# ActiTouch_Transmitter_Sheet1.net
KiCad netlist of a schematic drawn in Altium Designer
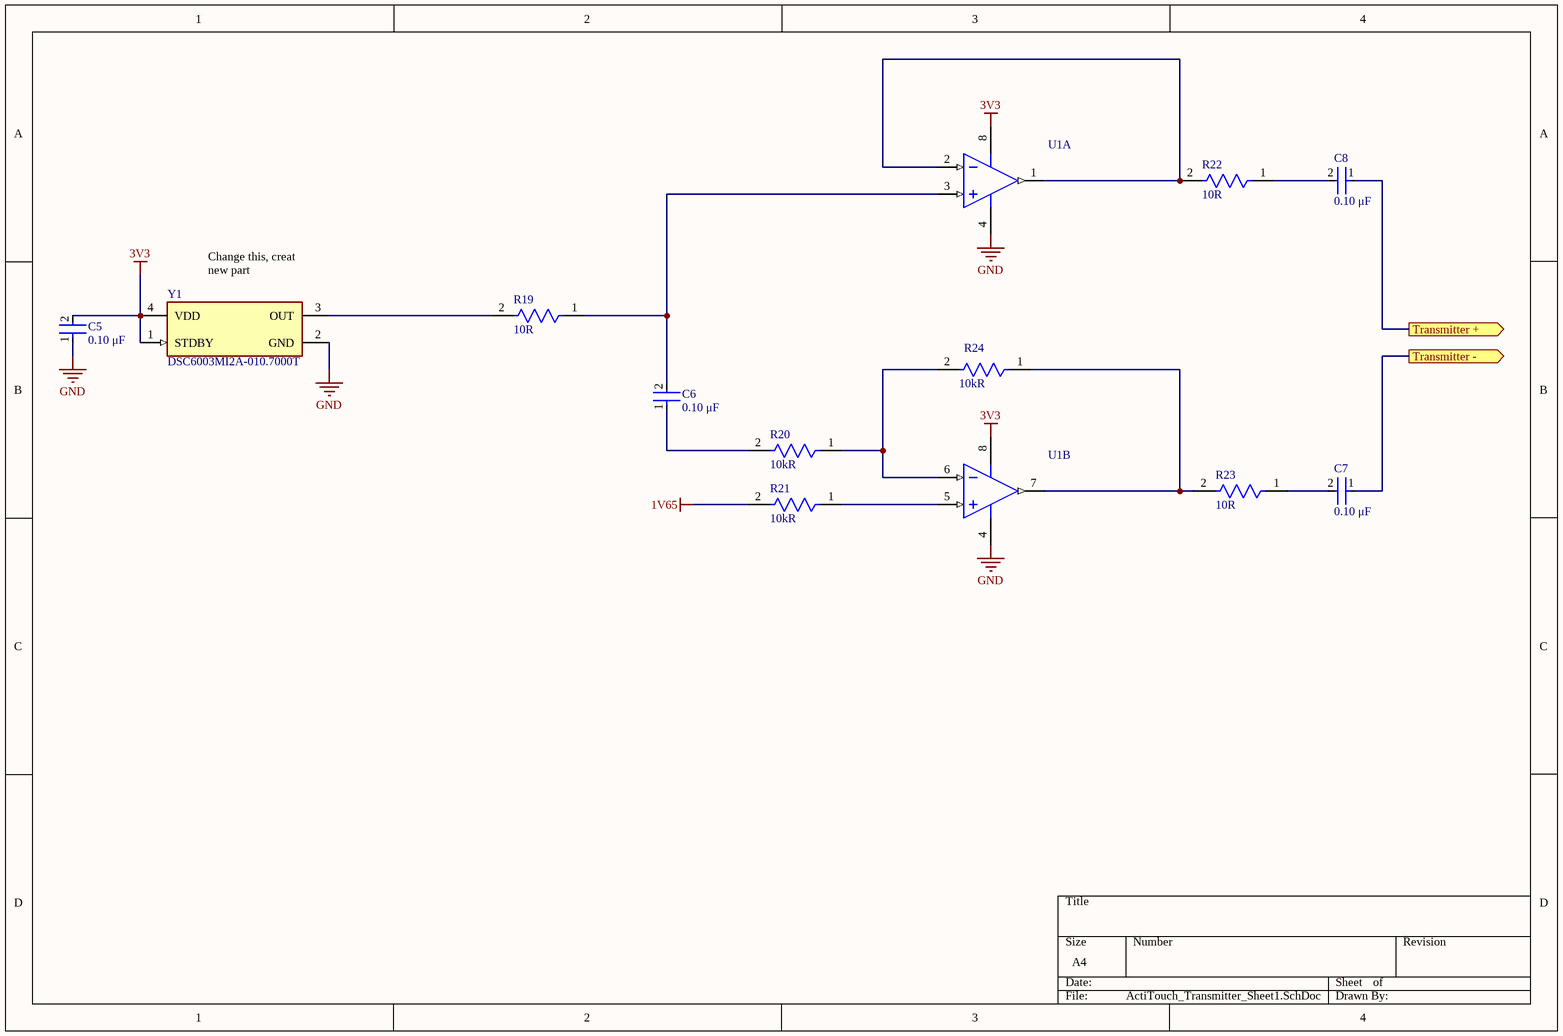
[diagram p0: ActiTouch_Transmitter_Sheet1.SchDoc]

(export (version "E")
  (design (tool "Eeschema 10.0.6"))
  (components
    (comp (ref "C5")
      (value "0.10 μF")
      (footprint "FP-C0603C-CF-MFG")
      (description "CAP CER 0.1UF 50V X7R 0603")
      (fields (field (name "TOLERANCE") "0.1") (field (name "MANUFACTURER") "KEMET"))
      (libsource (lib "Altium Content Vault") (part "b4654b650e69147ec39a6b967a45e02"))
    )
    (comp (ref "C6")
      (value "0.10 μF")
      (footprint "FP-C0603C-CF-MFG")
      (description "CAP CER 0.1UF 50V X7R 0603")
      (fields (field (name "TOLERANCE") "0.1") (field (name "MANUFACTURER") "KEMET"))
      (libsource (lib "Altium Content Vault") (part "b4654b650e69147ec39a6b967a45e02"))
    )
    (comp (ref "C7")
      (value "0.10 μF")
      (footprint "FP-C0603C-CF-MFG")
      (description "CAP CER 0.1UF 50V X7R 0603")
      (fields (field (name "TOLERANCE") "0.1") (field (name "MANUFACTURER") "KEMET"))
      (libsource (lib "Altium Content Vault") (part "b4654b650e69147ec39a6b967a45e02"))
    )
    (comp (ref "C8")
      (value "0.10 μF")
      (footprint "FP-C0603C-CF-MFG")
      (description "CAP CER 0.1UF 50V X7R 0603")
      (fields (field (name "TOLERANCE") "0.1") (field (name "MANUFACTURER") "KEMET"))
      (libsource (lib "Altium Content Vault") (part "b4654b650e69147ec39a6b967a45e02"))
    )
    (comp (ref "R19")
      (value "ESR03EZPJ101")
      (footprint "FP-ESR03-MFG")
      (description "100Ω ±5% 0.25W 0603 Anti-Surge Chip Resistor AEC-Q200")
      (fields (field (name "TOLERANCE") "5%") (field (name "RESISTANCE") "10R"))
      (libsource (lib "Altium Content Vault") (part "1029c3af85768c4190bb7ad29bc67b5"))
    )
    (comp (ref "R20")
      (value "ESR03EZPJ101")
      (footprint "FP-ESR03-MFG")
      (description "100Ω ±5% 0.25W 0603 Anti-Surge Chip Resistor AEC-Q200")
      (fields (field (name "TOLERANCE") "5%") (field (name "RESISTANCE") "10kR"))
      (libsource (lib "Altium Content Vault") (part "1029c3af85768c4190bb7ad29bc67b5"))
    )
    (comp (ref "R21")
      (value "ESR03EZPJ101")
      (footprint "FP-ESR03-MFG")
      (description "100Ω ±5% 0.25W 0603 Anti-Surge Chip Resistor AEC-Q200")
      (fields (field (name "TOLERANCE") "5%") (field (name "RESISTANCE") "10kR"))
      (libsource (lib "Altium Content Vault") (part "1029c3af85768c4190bb7ad29bc67b5"))
    )
    (comp (ref "R22")
      (value "ESR03EZPJ101")
      (footprint "FP-ESR03-MFG")
      (description "100Ω ±5% 0.25W 0603 Anti-Surge Chip Resistor AEC-Q200")
      (fields (field (name "TOLERANCE") "5%") (field (name "RESISTANCE") "10R"))
      (libsource (lib "Altium Content Vault") (part "1029c3af85768c4190bb7ad29bc67b5"))
    )
    (comp (ref "R23")
      (value "ESR03EZPJ101")
      (footprint "FP-ESR03-MFG")
      (description "100Ω ±5% 0.25W 0603 Anti-Surge Chip Resistor AEC-Q200")
      (fields (field (name "TOLERANCE") "5%") (field (name "RESISTANCE") "10R"))
      (libsource (lib "Altium Content Vault") (part "1029c3af85768c4190bb7ad29bc67b5"))
    )
    (comp (ref "R24")
      (value "ESR03EZPJ101")
      (footprint "FP-ESR03-MFG")
      (description "100Ω ±5% 0.25W 0603 Anti-Surge Chip Resistor AEC-Q200")
      (fields (field (name "TOLERANCE") "5%") (field (name "RESISTANCE") "10kR"))
      (libsource (lib "Altium Content Vault") (part "1029c3af85768c4190bb7ad29bc67b5"))
    )
    (comp (ref "U1")
      (value "OPA2836IDR")
      (footprint "D0008A_M")
      (fields (field (name "MANUFACTURER") "Texas Instruments"))
      (libsource (lib "Altium Content Vault") (part "TI-OPA2836D8"))
    )
    (comp (ref "Y1")
      (value "DSC6003MI2A-010.7000T")
      (footprint "FP-C04-1202-MFG")
      (libsource (lib "Altium Content Vault") (part "0879945b931ac6e5b4304121c4155e7"))
    )
  )
  (nets
    (net (code "1") (name "/Transmitter +") (class "Default")
      (node (ref "C8") (pin "1") (pinfunction "1_1") (pintype "passive"))
    )
    (net (code "2") (name "/Transmitter -") (class "Default")
      (node (ref "C7") (pin "1") (pinfunction "1_1") (pintype "passive"))
    )
    (net (code "3") (name "1V65") (class "Default")
      (node (ref "R21") (pin "2") (pinfunction "2_2") (pintype "passive"))
    )
    (net (code "4") (name "3V3") (class "Default")
      (node (ref "C5") (pin "2") (pinfunction "2_2") (pintype "passive"))
      (node (ref "U1") (pin "8") (pinfunction "VS+_8") (pintype "power_in"))
      (node (ref "Y1") (pin "1") (pinfunction "STDBY_1") (pintype "input"))
      (node (ref "Y1") (pin "4") (pinfunction "VDD_4") (pintype "power_in"))
    )
    (net (code "5") (name "GND") (class "Default")
      (node (ref "C5") (pin "1") (pinfunction "1_1") (pintype "passive"))
      (node (ref "U1") (pin "4") (pinfunction "VS-_4") (pintype "power_in"))
      (node (ref "Y1") (pin "2") (pinfunction "GND_2") (pintype "power_in"))
    )
    (net (code "6") (name "Net-(C6-Pad1)") (class "Default")
      (node (ref "C6") (pin "1") (pinfunction "1_1") (pintype "passive"))
      (node (ref "R20") (pin "2") (pinfunction "2_2") (pintype "passive"))
    )
    (net (code "7") (name "Net-(C7-Pad2)") (class "Default")
      (node (ref "C7") (pin "2") (pinfunction "2_2") (pintype "passive"))
      (node (ref "R23") (pin "1") (pinfunction "1_1") (pintype "passive"))
    )
    (net (code "8") (name "Net-(C8-Pad2)") (class "Default")
      (node (ref "C8") (pin "2") (pinfunction "2_2") (pintype "passive"))
      (node (ref "R22") (pin "1") (pinfunction "1_1") (pintype "passive"))
    )
    (net (code "9") (name "Net-(U1A-VIN1+)") (class "Default")
      (node (ref "C6") (pin "2") (pinfunction "2_2") (pintype "passive"))
      (node (ref "R19") (pin "1") (pinfunction "1_1") (pintype "passive"))
      (node (ref "U1") (pin "3") (pinfunction "VIN1+_3") (pintype "input"))
    )
    (net (code "10") (name "Net-(U1A-VIN1-)") (class "Default")
      (node (ref "R22") (pin "2") (pinfunction "2_2") (pintype "passive"))
      (node (ref "U1") (pin "1") (pinfunction "VOUT1_1") (pintype "output"))
      (node (ref "U1") (pin "2") (pinfunction "VIN1-_2") (pintype "input"))
    )
    (net (code "11") (name "Net-(U1B-VIN2+)") (class "Default")
      (node (ref "R21") (pin "1") (pinfunction "1_1") (pintype "passive"))
      (node (ref "U1") (pin "5") (pinfunction "VIN2+_5") (pintype "input"))
    )
    (net (code "12") (name "Net-(U1B-VIN2-)") (class "Default")
      (node (ref "R20") (pin "1") (pinfunction "1_1") (pintype "passive"))
      (node (ref "R24") (pin "2") (pinfunction "2_2") (pintype "passive"))
      (node (ref "U1") (pin "6") (pinfunction "VIN2-_6") (pintype "input"))
    )
    (net (code "13") (name "Net-(U1B-VOUT2)") (class "Default")
      (node (ref "R23") (pin "2") (pinfunction "2_2") (pintype "passive"))
      (node (ref "R24") (pin "1") (pinfunction "1_1") (pintype "passive"))
      (node (ref "U1") (pin "7") (pinfunction "VOUT2_7") (pintype "output"))
    )
    (net (code "14") (name "Net-(Y1-OUT)") (class "Default")
      (node (ref "R19") (pin "2") (pinfunction "2_2") (pintype "passive"))
      (node (ref "Y1") (pin "3") (pinfunction "OUT_3") (pintype "passive"))
    )
  )
)
